# T_l_commande.net
KiCad netlist of a schematic drawn in Altium Designer
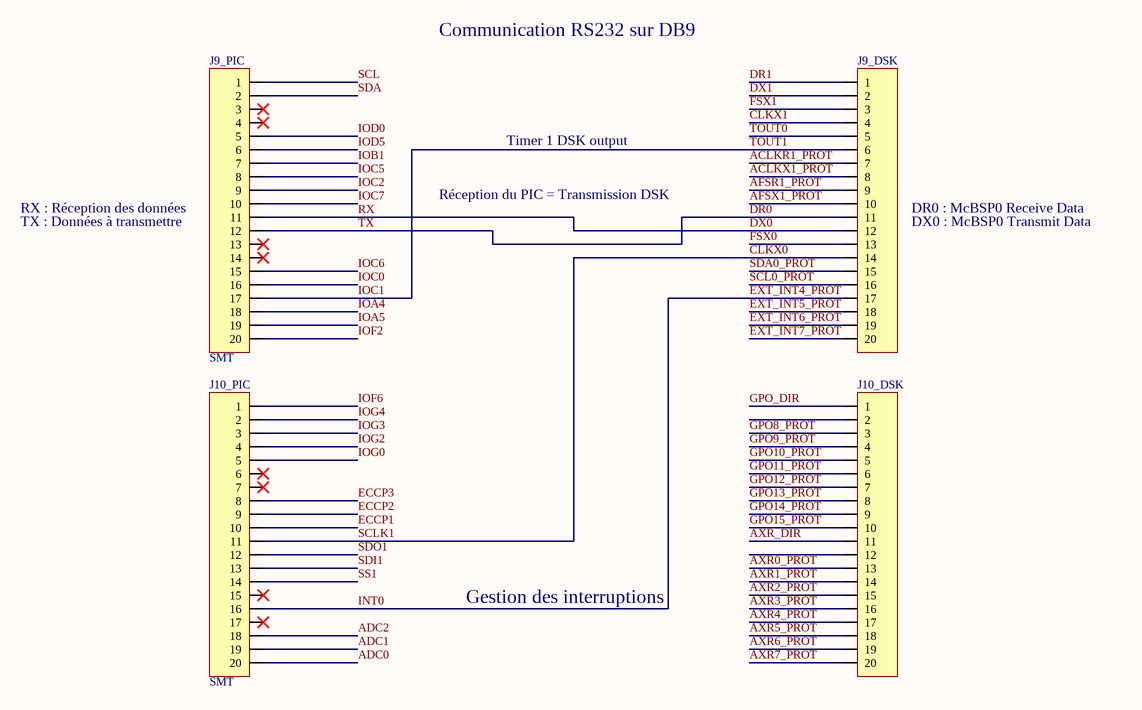
[diagram p0: Télécommande.SchDoc]

(export (version "E")
  (design (tool "Eeschema 10.0.6"))
  (components
    (comp (ref "J9_DSK")
      (value "Conn20pinsF")
      (footprint "Conn_20_SMT")
      (description "Connecteur 20 pins F - pitch = 100mils")
      (fields
        (field (name "MANUFACTURER") "Sullins Connector Solutions")
        (field (name "MFG PART NUMBER") "NPTC102KFMS-RC")
        (field (name "CREATEDBY") "Olivier Bernard")
        (field (name "VERIFIEDBY") "*")
      )
      (libsource (lib "SchLib_PCBs5") (part "Conn20pinsF"))
    )
    (comp (ref "J9_PIC")
      (value "Conn20pinsF")
      (footprint "Conn_20_SMT")
      (description "Connecteur 20 pins F - pitch = 100mils")
      (fields
        (field (name "MANUFACTURER") "Sullins Connector Solutions")
        (field (name "MFG PART NUMBER") "NPTC102KFMS-RC")
        (field (name "PACKAGE") "SMT")
        (field (name "CREATEDBY") "Olivier Bernard")
        (field (name "VERIFIEDBY") "*")
      )
      (libsource (lib "") (part "Conn20pinsF_1"))
    )
    (comp (ref "J10_DSK")
      (value "Conn20pinsF")
      (footprint "Conn_20_SMT")
      (description "Connecteur 20 pins F - pitch = 100mils")
      (fields
        (field (name "MANUFACTURER") "Sullins Connector Solutions")
        (field (name "MFG PART NUMBER") "NPTC102KFMS-RC")
        (field (name "CREATEDBY") "Olivier Bernard")
        (field (name "VERIFIEDBY") "*")
      )
      (libsource (lib "SchLib_PCBs5") (part "Conn20pinsF"))
    )
    (comp (ref "J10_PIC")
      (value "Conn20pinsF")
      (footprint "Conn_20_SMT")
      (description "Connecteur 20 pins F - pitch = 100mils")
      (fields
        (field (name "MANUFACTURER") "Sullins Connector Solutions")
        (field (name "MFG PART NUMBER") "NPTC102KFMS-RC")
        (field (name "PACKAGE") "SMT")
        (field (name "CREATEDBY") "Olivier Bernard")
        (field (name "VERIFIEDBY") "*")
      )
      (libsource (lib "") (part "Conn20pinsF_1"))
    )
  )
  (nets
    (net (code "1") (name "/ACLKR1_PROT") (class "Default")
      (node (ref "J9_DSK") (pin "7") (pinfunction "7_7") (pintype "passive"))
    )
    (net (code "2") (name "/ACLKX1_PROT") (class "Default")
      (node (ref "J9_DSK") (pin "8") (pinfunction "8_8") (pintype "passive"))
    )
    (net (code "3") (name "/ADC0") (class "Default")
      (node (ref "J10_PIC") (pin "20") (pinfunction "20_20") (pintype "passive"))
    )
    (net (code "4") (name "/ADC1") (class "Default")
      (node (ref "J10_PIC") (pin "19") (pinfunction "19_19") (pintype "passive"))
    )
    (net (code "5") (name "/ADC2") (class "Default")
      (node (ref "J10_PIC") (pin "18") (pinfunction "18_18") (pintype "passive"))
    )
    (net (code "6") (name "/AFSR1_PROT") (class "Default")
      (node (ref "J9_DSK") (pin "9") (pinfunction "9_9") (pintype "passive"))
    )
    (net (code "7") (name "/AFSX1_PROT") (class "Default")
      (node (ref "J9_DSK") (pin "10") (pinfunction "10_10") (pintype "passive"))
    )
    (net (code "8") (name "/AXR0_PROT") (class "Default")
      (node (ref "J10_DSK") (pin "13") (pinfunction "13_13") (pintype "passive"))
    )
    (net (code "9") (name "/AXR1_PROT") (class "Default")
      (node (ref "J10_DSK") (pin "14") (pinfunction "14_14") (pintype "passive"))
    )
    (net (code "10") (name "/AXR2_PROT") (class "Default")
      (node (ref "J10_DSK") (pin "15") (pinfunction "15_15") (pintype "passive"))
    )
    (net (code "11") (name "/AXR3_PROT") (class "Default")
      (node (ref "J10_DSK") (pin "16") (pinfunction "16_16") (pintype "passive"))
    )
    (net (code "12") (name "/AXR4_PROT") (class "Default")
      (node (ref "J10_DSK") (pin "17") (pinfunction "17_17") (pintype "passive"))
    )
    (net (code "13") (name "/AXR5_PROT") (class "Default")
      (node (ref "J10_DSK") (pin "18") (pinfunction "18_18") (pintype "passive"))
    )
    (net (code "14") (name "/AXR6_PROT") (class "Default")
      (node (ref "J10_DSK") (pin "19") (pinfunction "19_19") (pintype "passive"))
    )
    (net (code "15") (name "/AXR7_PROT") (class "Default")
      (node (ref "J10_DSK") (pin "20") (pinfunction "20_20") (pintype "passive"))
    )
    (net (code "16") (name "/AXR_DIR") (class "Default")
      (node (ref "J10_DSK") (pin "11") (pinfunction "11_11") (pintype "passive"))
    )
    (net (code "17") (name "/CLKX0") (class "Default")
      (node (ref "J10_PIC") (pin "11") (pinfunction "11_11") (pintype "passive"))
      (node (ref "J9_DSK") (pin "14") (pinfunction "14_14") (pintype "passive"))
    )
    (net (code "18") (name "/CLKX1") (class "Default")
      (node (ref "J9_DSK") (pin "4") (pinfunction "4_4") (pintype "passive"))
    )
    (net (code "19") (name "/DR0") (class "Default")
      (node (ref "J9_DSK") (pin "11") (pinfunction "11_11") (pintype "passive"))
      (node (ref "J9_PIC") (pin "12") (pinfunction "12_12") (pintype "passive"))
    )
    (net (code "20") (name "/DR1") (class "Default")
      (node (ref "J9_DSK") (pin "1") (pinfunction "1_1") (pintype "passive"))
    )
    (net (code "21") (name "/DX0") (class "Default")
      (node (ref "J9_DSK") (pin "12") (pinfunction "12_12") (pintype "passive"))
      (node (ref "J9_PIC") (pin "11") (pinfunction "11_11") (pintype "passive"))
    )
    (net (code "22") (name "/DX1") (class "Default")
      (node (ref "J9_DSK") (pin "2") (pinfunction "2_2") (pintype "passive"))
    )
    (net (code "23") (name "/ECCP1") (class "Default")
      (node (ref "J10_PIC") (pin "10") (pinfunction "10_10") (pintype "passive"))
    )
    (net (code "24") (name "/ECCP2") (class "Default")
      (node (ref "J10_PIC") (pin "9") (pinfunction "9_9") (pintype "passive"))
    )
    (net (code "25") (name "/ECCP3") (class "Default")
      (node (ref "J10_PIC") (pin "8") (pinfunction "8_8") (pintype "passive"))
    )
    (net (code "26") (name "/EXT_INT4_PROT") (class "Default")
      (node (ref "J10_PIC") (pin "16") (pinfunction "16_16") (pintype "passive"))
      (node (ref "J9_DSK") (pin "17") (pinfunction "17_17") (pintype "passive"))
    )
    (net (code "27") (name "/EXT_INT5_PROT") (class "Default")
      (node (ref "J9_DSK") (pin "18") (pinfunction "18_18") (pintype "passive"))
    )
    (net (code "28") (name "/EXT_INT6_PROT") (class "Default")
      (node (ref "J9_DSK") (pin "19") (pinfunction "19_19") (pintype "passive"))
    )
    (net (code "29") (name "/EXT_INT7_PROT") (class "Default")
      (node (ref "J9_DSK") (pin "20") (pinfunction "20_20") (pintype "passive"))
    )
    (net (code "30") (name "/FSX0") (class "Default")
      (node (ref "J9_DSK") (pin "13") (pinfunction "13_13") (pintype "passive"))
    )
    (net (code "31") (name "/FSX1") (class "Default")
      (node (ref "J9_DSK") (pin "3") (pinfunction "3_3") (pintype "passive"))
    )
    (net (code "32") (name "/GPO8_PROT") (class "Default")
      (node (ref "J10_DSK") (pin "3") (pinfunction "3_3") (pintype "passive"))
    )
    (net (code "33") (name "/GPO9_PROT") (class "Default")
      (node (ref "J10_DSK") (pin "4") (pinfunction "4_4") (pintype "passive"))
    )
    (net (code "34") (name "/GPO10_PROT") (class "Default")
      (node (ref "J10_DSK") (pin "5") (pinfunction "5_5") (pintype "passive"))
    )
    (net (code "35") (name "/GPO11_PROT") (class "Default")
      (node (ref "J10_DSK") (pin "6") (pinfunction "6_6") (pintype "passive"))
    )
    (net (code "36") (name "/GPO12_PROT") (class "Default")
      (node (ref "J10_DSK") (pin "7") (pinfunction "7_7") (pintype "passive"))
    )
    (net (code "37") (name "/GPO13_PROT") (class "Default")
      (node (ref "J10_DSK") (pin "8") (pinfunction "8_8") (pintype "passive"))
    )
    (net (code "38") (name "/GPO14_PROT") (class "Default")
      (node (ref "J10_DSK") (pin "9") (pinfunction "9_9") (pintype "passive"))
    )
    (net (code "39") (name "/GPO15_PROT") (class "Default")
      (node (ref "J10_DSK") (pin "10") (pinfunction "10_10") (pintype "passive"))
    )
    (net (code "40") (name "/GPO_DIR") (class "Default")
      (node (ref "J10_DSK") (pin "1") (pinfunction "1_1") (pintype "passive"))
    )
    (net (code "41") (name "/IOA4") (class "Default")
      (node (ref "J9_PIC") (pin "18") (pinfunction "18_18") (pintype "passive"))
    )
    (net (code "42") (name "/IOA5") (class "Default")
      (node (ref "J9_PIC") (pin "19") (pinfunction "19_19") (pintype "passive"))
    )
    (net (code "43") (name "/IOB1") (class "Default")
      (node (ref "J9_PIC") (pin "7") (pinfunction "7_7") (pintype "passive"))
    )
    (net (code "44") (name "/IOC0") (class "Default")
      (node (ref "J9_PIC") (pin "16") (pinfunction "16_16") (pintype "passive"))
    )
    (net (code "45") (name "/IOC1") (class "Default")
      (node (ref "J9_DSK") (pin "6") (pinfunction "6_6") (pintype "passive"))
      (node (ref "J9_PIC") (pin "17") (pinfunction "17_17") (pintype "passive"))
    )
    (net (code "46") (name "/IOC2") (class "Default")
      (node (ref "J9_PIC") (pin "9") (pinfunction "9_9") (pintype "passive"))
    )
    (net (code "47") (name "/IOC5") (class "Default")
      (node (ref "J9_PIC") (pin "8") (pinfunction "8_8") (pintype "passive"))
    )
    (net (code "48") (name "/IOC6") (class "Default")
      (node (ref "J9_PIC") (pin "15") (pinfunction "15_15") (pintype "passive"))
    )
    (net (code "49") (name "/IOC7") (class "Default")
      (node (ref "J9_PIC") (pin "10") (pinfunction "10_10") (pintype "passive"))
    )
    (net (code "50") (name "/IOD0") (class "Default")
      (node (ref "J9_PIC") (pin "5") (pinfunction "5_5") (pintype "passive"))
    )
    (net (code "51") (name "/IOD5") (class "Default")
      (node (ref "J9_PIC") (pin "6") (pinfunction "6_6") (pintype "passive"))
    )
    (net (code "52") (name "/IOF2") (class "Default")
      (node (ref "J9_PIC") (pin "20") (pinfunction "20_20") (pintype "passive"))
    )
    (net (code "53") (name "/IOF6") (class "Default")
      (node (ref "J10_PIC") (pin "1") (pinfunction "1_1") (pintype "passive"))
    )
    (net (code "54") (name "/IOG0") (class "Default")
      (node (ref "J10_PIC") (pin "5") (pinfunction "5_5") (pintype "passive"))
    )
    (net (code "55") (name "/IOG2") (class "Default")
      (node (ref "J10_PIC") (pin "4") (pinfunction "4_4") (pintype "passive"))
    )
    (net (code "56") (name "/IOG3") (class "Default")
      (node (ref "J10_PIC") (pin "3") (pinfunction "3_3") (pintype "passive"))
    )
    (net (code "57") (name "/IOG4") (class "Default")
      (node (ref "J10_PIC") (pin "2") (pinfunction "2_2") (pintype "passive"))
    )
    (net (code "58") (name "/SCL") (class "Default")
      (node (ref "J9_PIC") (pin "1") (pinfunction "1_1") (pintype "passive"))
    )
    (net (code "59") (name "/SCL0_PROT") (class "Default")
      (node (ref "J9_DSK") (pin "16") (pinfunction "16_16") (pintype "passive"))
    )
    (net (code "60") (name "/SDA") (class "Default")
      (node (ref "J9_PIC") (pin "2") (pinfunction "2_2") (pintype "passive"))
    )
    (net (code "61") (name "/SDA0_PROT") (class "Default")
      (node (ref "J9_DSK") (pin "15") (pinfunction "15_15") (pintype "passive"))
    )
    (net (code "62") (name "/SDI1") (class "Default")
      (node (ref "J10_PIC") (pin "13") (pinfunction "13_13") (pintype "passive"))
    )
    (net (code "63") (name "/SDO1") (class "Default")
      (node (ref "J10_PIC") (pin "12") (pinfunction "12_12") (pintype "passive"))
    )
    (net (code "64") (name "/SS1") (class "Default")
      (node (ref "J10_PIC") (pin "14") (pinfunction "14_14") (pintype "passive"))
    )
    (net (code "65") (name "/TOUT0") (class "Default")
      (node (ref "J9_DSK") (pin "5") (pinfunction "5_5") (pintype "passive"))
    )
    (net (code "66") (name "unconnected-(J9_PIC-Pad3)") (class "Default")
      (node (ref "J9_PIC") (pin "3") (pinfunction "3_3") (pintype "passive+no_connect"))
    )
    (net (code "67") (name "unconnected-(J9_PIC-Pad4)") (class "Default")
      (node (ref "J9_PIC") (pin "4") (pinfunction "4_4") (pintype "passive+no_connect"))
    )
    (net (code "68") (name "unconnected-(J9_PIC-Pad13)") (class "Default")
      (node (ref "J9_PIC") (pin "13") (pinfunction "13_13") (pintype "passive+no_connect"))
    )
    (net (code "69") (name "unconnected-(J9_PIC-Pad14)") (class "Default")
      (node (ref "J9_PIC") (pin "14") (pinfunction "14_14") (pintype "passive+no_connect"))
    )
    (net (code "70") (name "unconnected-(J10_DSK-Pad2)") (class "Default")
      (node (ref "J10_DSK") (pin "2") (pinfunction "2_2") (pintype "passive"))
    )
    (net (code "71") (name "unconnected-(J10_DSK-Pad12)") (class "Default")
      (node (ref "J10_DSK") (pin "12") (pinfunction "12_12") (pintype "passive"))
    )
    (net (code "72") (name "unconnected-(J10_PIC-Pad6)") (class "Default")
      (node (ref "J10_PIC") (pin "6") (pinfunction "6_6") (pintype "passive+no_connect"))
    )
    (net (code "73") (name "unconnected-(J10_PIC-Pad7)") (class "Default")
      (node (ref "J10_PIC") (pin "7") (pinfunction "7_7") (pintype "passive+no_connect"))
    )
    (net (code "74") (name "unconnected-(J10_PIC-Pad15)") (class "Default")
      (node (ref "J10_PIC") (pin "15") (pinfunction "15_15") (pintype "passive+no_connect"))
    )
    (net (code "75") (name "unconnected-(J10_PIC-Pad17)") (class "Default")
      (node (ref "J10_PIC") (pin "17") (pinfunction "17_17") (pintype "passive+no_connect"))
    )
  )
)
